# finalprojeagle.net
KiCad netlist of a schematic drawn in EAGLE
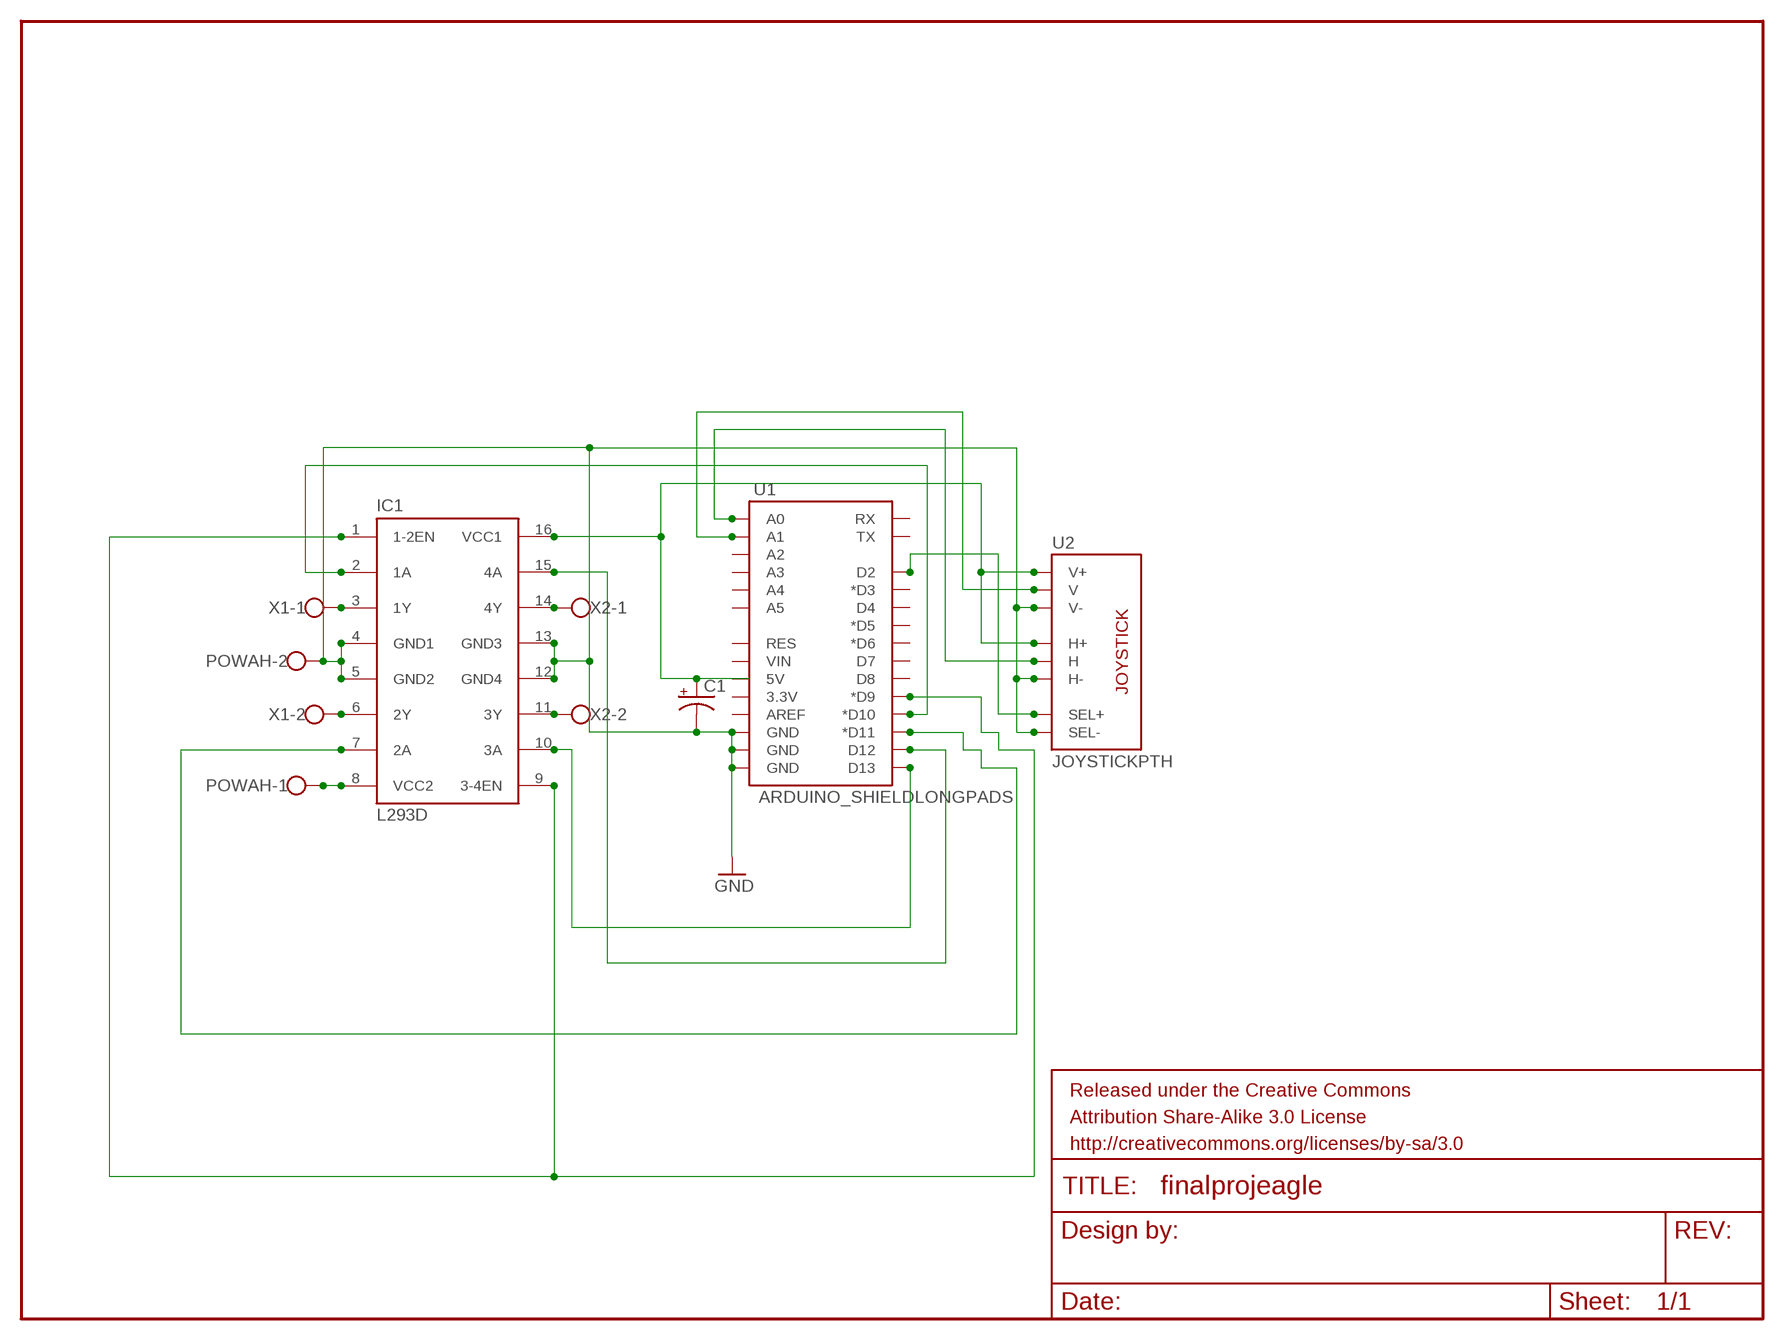
[diagram p0: schematic, sheet 1]

(export (version "E")
  (design (tool "Eeschema 10.0.6"))
  (components
    (comp (ref "C1")
      (value "CAP_POLPTH2")
      (footprint "eagle-import:CPOL-RADIAL-10UF-25V")
      (libsource (lib "eagle-import") (part "CAP_POLPTH2"))
    )
    (comp (ref "FRAME1")
      (value "FRAME-LETTER")
      (footprint "eagle-import:CREATIVE_COMMONS")
      (libsource (lib "eagle-import") (part "FRAME-LETTER"))
    )
    (comp (ref "IC1")
      (value "L293D")
      (footprint "eagle-import:DIL16")
      (libsource (lib "eagle-import") (part "L293D"))
    )
    (comp (ref "POWAH")
      (value "W237-102")
      (footprint "eagle-import:W237-102")
      (fields (field (name "MPN") "237-102"))
      (libsource (lib "eagle-import") (part "W237-102"))
    )
    (comp (ref "U1")
      (value "ARDUINO_SHIELDLONGPADS")
      (footprint "eagle-import:DUEMILANOVE_SHIELD_LONGPADS")
      (libsource (lib "eagle-import") (part "ARDUINO_SHIELDLONGPADS"))
    )
    (comp (ref "U2")
      (value "JOYSTICKPTH")
      (footprint "eagle-import:JOYSTICK")
      (libsource (lib "eagle-import") (part "JOYSTICKPTH"))
    )
    (comp (ref "X1")
      (value "W237-102")
      (footprint "eagle-import:W237-102")
      (fields (field (name "MPN") "237-102"))
      (libsource (lib "eagle-import") (part "W237-102"))
    )
    (comp (ref "X2")
      (value "W237-102")
      (footprint "eagle-import:W237-102")
      (fields (field (name "MPN") "237-102"))
      (libsource (lib "eagle-import") (part "W237-102"))
    )
  )
  (nets
    (net (code "1") (name "GND") (class "Default")
      (node (ref "C1") (pin "2") (pinfunction "-_2") (pintype "passive"))
      (node (ref "IC1") (pin "12") (pinfunction "GND4_12") (pintype "power_in"))
      (node (ref "IC1") (pin "13") (pinfunction "GND3_13") (pintype "power_in"))
      (node (ref "IC1") (pin "4") (pinfunction "GND1_4") (pintype "power_in"))
      (node (ref "IC1") (pin "5") (pinfunction "GND2_5") (pintype "power_in"))
      (node (ref "POWAH") (pin "2") (pinfunction "KL_2") (pintype "passive"))
      (node (ref "U1") (pin "GND@0") (pinfunction "GND_GND@0") (pintype "bidirectional"))
      (node (ref "U1") (pin "GND@1") (pinfunction "GND_GND@1") (pintype "bidirectional"))
      (node (ref "U1") (pin "GND@2") (pinfunction "GND_GND@2") (pintype "bidirectional"))
      (node (ref "U2") (pin "B2A") (pinfunction "SEL-_B2A") (pintype "bidirectional"))
      (node (ref "U2") (pin "H3") (pinfunction "H-_H3") (pintype "bidirectional"))
      (node (ref "U2") (pin "V3") (pinfunction "V-_V3") (pintype "bidirectional"))
    )
    (net (code "2") (name "Net-(C1-+)") (class "Default")
      (node (ref "C1") (pin "1") (pinfunction "+_1") (pintype "passive"))
      (node (ref "IC1") (pin "16") (pinfunction "VCC1_16") (pintype "power_in"))
      (node (ref "U1") (pin "5V") (pinfunction "5V_5V") (pintype "bidirectional"))
      (node (ref "U2") (pin "H1") (pinfunction "H+_H1") (pintype "bidirectional"))
      (node (ref "U2") (pin "V1") (pinfunction "V+_V1") (pintype "bidirectional"))
    )
    (net (code "3") (name "Net-(IC1-1-2EN)") (class "Default")
      (node (ref "IC1") (pin "1") (pinfunction "1-2EN_1") (pintype "input"))
      (node (ref "IC1") (pin "9") (pinfunction "3-4EN_9") (pintype "input"))
      (node (ref "U1") (pin "D9") (pinfunction "*D9_D9") (pintype "bidirectional"))
    )
    (net (code "4") (name "Net-(IC1-1A)") (class "Default")
      (node (ref "IC1") (pin "2") (pinfunction "1A_2") (pintype "input"))
      (node (ref "U1") (pin "D10") (pinfunction "*D10_D10") (pintype "bidirectional"))
    )
    (net (code "5") (name "Net-(IC1-1Y)") (class "Default")
      (node (ref "IC1") (pin "3") (pinfunction "1Y_3") (pintype "output"))
      (node (ref "X1") (pin "1") (pinfunction "KL_1") (pintype "passive"))
    )
    (net (code "6") (name "Net-(IC1-2A)") (class "Default")
      (node (ref "IC1") (pin "7") (pinfunction "2A_7") (pintype "input"))
      (node (ref "U1") (pin "D11") (pinfunction "*D11_D11") (pintype "bidirectional"))
    )
    (net (code "7") (name "Net-(IC1-2Y)") (class "Default")
      (node (ref "IC1") (pin "6") (pinfunction "2Y_6") (pintype "output"))
      (node (ref "X1") (pin "2") (pinfunction "KL_2") (pintype "passive"))
    )
    (net (code "8") (name "Net-(IC1-3A)") (class "Default")
      (node (ref "IC1") (pin "10") (pinfunction "3A_10") (pintype "input"))
      (node (ref "U1") (pin "D13") (pinfunction "D13_D13") (pintype "bidirectional"))
    )
    (net (code "9") (name "Net-(IC1-3Y)") (class "Default")
      (node (ref "IC1") (pin "11") (pinfunction "3Y_11") (pintype "output"))
      (node (ref "X2") (pin "2") (pinfunction "KL_2") (pintype "passive"))
    )
    (net (code "10") (name "Net-(IC1-4A)") (class "Default")
      (node (ref "IC1") (pin "15") (pinfunction "4A_15") (pintype "input"))
      (node (ref "U1") (pin "D12") (pinfunction "D12_D12") (pintype "bidirectional"))
    )
    (net (code "11") (name "Net-(IC1-4Y)") (class "Default")
      (node (ref "IC1") (pin "14") (pinfunction "4Y_14") (pintype "output"))
      (node (ref "X2") (pin "1") (pinfunction "KL_1") (pintype "passive"))
    )
    (net (code "12") (name "Net-(IC1-VCC2)") (class "Default")
      (node (ref "IC1") (pin "8") (pinfunction "VCC2_8") (pintype "power_in"))
      (node (ref "POWAH") (pin "1") (pinfunction "KL_1") (pintype "passive"))
    )
    (net (code "13") (name "Net-(U2-H)") (class "Default")
      (node (ref "U1") (pin "A0") (pinfunction "A0_A0") (pintype "bidirectional"))
      (node (ref "U2") (pin "H2") (pinfunction "H_H2") (pintype "bidirectional"))
    )
    (net (code "14") (name "Net-(U2-SEL+)") (class "Default")
      (node (ref "U1") (pin "D2") (pinfunction "D2_D2") (pintype "bidirectional"))
      (node (ref "U2") (pin "B1A") (pinfunction "SEL+_B1A") (pintype "bidirectional"))
    )
    (net (code "15") (name "Net-(U2-V)") (class "Default")
      (node (ref "U1") (pin "A1") (pinfunction "A1_A1") (pintype "bidirectional"))
      (node (ref "U2") (pin "V2") (pinfunction "V_V2") (pintype "bidirectional"))
    )
    (net (code "16") (name "unconnected-(U1-*D3-PadD3)") (class "Default")
      (node (ref "U1") (pin "D3") (pinfunction "*D3_D3") (pintype "bidirectional"))
    )
    (net (code "17") (name "unconnected-(U1-*D5-PadD5)") (class "Default")
      (node (ref "U1") (pin "D5") (pinfunction "*D5_D5") (pintype "bidirectional"))
    )
    (net (code "18") (name "unconnected-(U1-*D6-PadD6)") (class "Default")
      (node (ref "U1") (pin "D6") (pinfunction "*D6_D6") (pintype "bidirectional"))
    )
    (net (code "19") (name "unconnected-(U1-Pad3.3V)") (class "Default")
      (node (ref "U1") (pin "3.3V") (pinfunction "3.3V_3.3V") (pintype "bidirectional"))
    )
    (net (code "20") (name "unconnected-(U1-PadA2)") (class "Default")
      (node (ref "U1") (pin "A2") (pinfunction "A2_A2") (pintype "bidirectional"))
    )
    (net (code "21") (name "unconnected-(U1-PadA3)") (class "Default")
      (node (ref "U1") (pin "A3") (pinfunction "A3_A3") (pintype "bidirectional"))
    )
    (net (code "22") (name "unconnected-(U1-PadA4)") (class "Default")
      (node (ref "U1") (pin "A4") (pinfunction "A4_A4") (pintype "bidirectional"))
    )
    (net (code "23") (name "unconnected-(U1-PadA5)") (class "Default")
      (node (ref "U1") (pin "A5") (pinfunction "A5_A5") (pintype "bidirectional"))
    )
    (net (code "24") (name "unconnected-(U1-PadAREF)") (class "Default")
      (node (ref "U1") (pin "AREF") (pinfunction "AREF_AREF") (pintype "bidirectional"))
    )
    (net (code "25") (name "unconnected-(U1-PadD4)") (class "Default")
      (node (ref "U1") (pin "D4") (pinfunction "D4_D4") (pintype "bidirectional"))
    )
    (net (code "26") (name "unconnected-(U1-PadD7)") (class "Default")
      (node (ref "U1") (pin "D7") (pinfunction "D7_D7") (pintype "bidirectional"))
    )
    (net (code "27") (name "unconnected-(U1-PadD8)") (class "Default")
      (node (ref "U1") (pin "D8") (pinfunction "D8_D8") (pintype "bidirectional"))
    )
    (net (code "28") (name "unconnected-(U1-PadRES)") (class "Default")
      (node (ref "U1") (pin "RES") (pinfunction "RES_RES") (pintype "bidirectional"))
    )
    (net (code "29") (name "unconnected-(U1-PadRX)") (class "Default")
      (node (ref "U1") (pin "RX") (pinfunction "RX_RX") (pintype "bidirectional"))
    )
    (net (code "30") (name "unconnected-(U1-PadTX)") (class "Default")
      (node (ref "U1") (pin "TX") (pinfunction "TX_TX") (pintype "bidirectional"))
    )
    (net (code "31") (name "unconnected-(U1-PadVIN)") (class "Default")
      (node (ref "U1") (pin "VIN") (pinfunction "VIN_VIN") (pintype "bidirectional"))
    )
  )
)
